# driver.net
KiCad netlist of a schematic drawn in Altium Designer
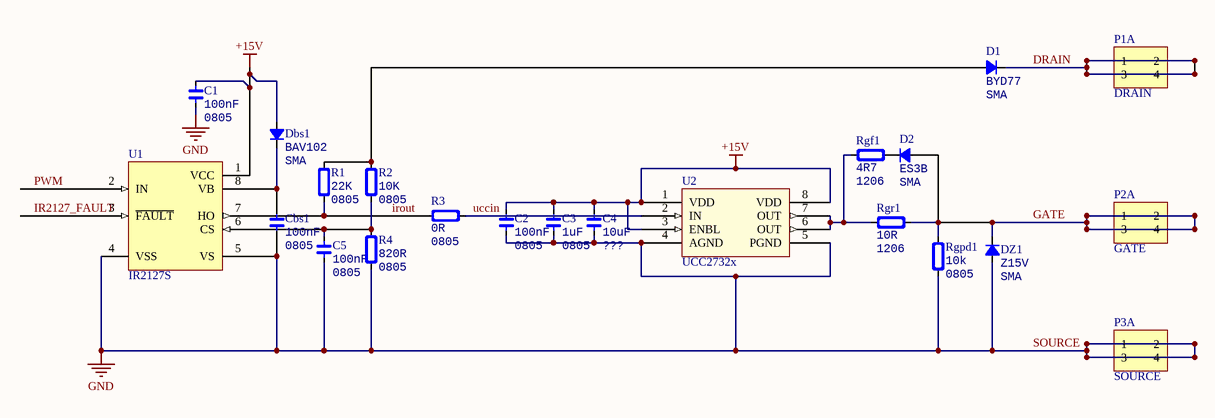
[diagram p0: driver.SchDoc]

(export (version "E")
  (design (tool "Eeschema 10.0.6"))
  (components
    (comp (ref "C1")
      (value "100nF")
      (footprint "0805C")
      (description "Capacitor")
      (fields (field (name "TYPE") "0805"))
      (libsource (lib "SCH_Passive") (part "Cap_0805"))
    )
    (comp (ref "C2")
      (value "100nF")
      (footprint "0805C")
      (description "Capacitor")
      (fields (field (name "TYPE") "0805"))
      (libsource (lib "SCH_Passive") (part "Cap_0805"))
    )
    (comp (ref "C3")
      (value "1uF")
      (footprint "0805C")
      (description "Capacitor")
      (fields (field (name "TYPE") "0805"))
      (libsource (lib "SCH_Passive") (part "Cap_0805"))
    )
    (comp (ref "C4")
      (value "10uF")
      (footprint "0805C")
      (description "Capacitor")
      (fields (field (name "TYPE") "???"))
      (libsource (lib "SCH_Passive") (part "Cap_0805"))
    )
    (comp (ref "C5")
      (value "100nF")
      (footprint "0805C")
      (description "Capacitor")
      (fields (field (name "TYPE") "0805"))
      (libsource (lib "SCH_Passive") (part "Cap_0805"))
    )
    (comp (ref "Cbs1")
      (value "100nF")
      (footprint "0805C")
      (description "Capacitor")
      (fields (field (name "TYPE") "0805"))
      (libsource (lib "SCH_Passive") (part "Cap_0805"))
    )
    (comp (ref "D1")
      (value "BYD77")
      (footprint "DSO-C2/X2.3")
      (description "Diode")
      (fields (field (name "TYPE") "SMA"))
      (libsource (lib "SCH_Active") (part "Diode_SMA"))
    )
    (comp (ref "D2")
      (value "ES3B")
      (footprint "DSO-C2/X2.3")
      (description "Diode")
      (fields (field (name "TYPE") "SMA"))
      (libsource (lib "SCH_Active") (part "Diode_SMA"))
    )
    (comp (ref "Dbs1")
      (value "BAV102")
      (footprint "DSO-C2/X2.3")
      (description "Diode")
      (fields (field (name "TYPE") "SMA"))
      (libsource (lib "SCH_Active") (part "Diode_SMA"))
    )
    (comp (ref "DZ1")
      (value "Z15V")
      (footprint "DSO-C2/X2.3")
      (description "Diode")
      (fields (field (name "TYPE") "SMA"))
      (libsource (lib "SCH_Active") (part "Diode_SMA"))
    )
    (comp (ref "P1A")
      (value "DRAIN")
      (footprint "HDR2X2")
      (description "Header, 2-Pin, Dual row")
      (fields (field (name "PUBLISHER") "Altium Limited"))
      (libsource (lib "Miscellaneous Connectors") (part "Header 2X2"))
    )
    (comp (ref "P2A")
      (value "GATE")
      (footprint "HDR2X2")
      (description "Header, 2-Pin, Dual row")
      (fields (field (name "PUBLISHER") "Altium Limited"))
      (libsource (lib "Miscellaneous Connectors") (part "Header 2X2"))
    )
    (comp (ref "P3A")
      (value "SOURCE")
      (footprint "HDR2X2")
      (description "Header, 2-Pin, Dual row")
      (fields (field (name "PUBLISHER") "Altium Limited"))
      (libsource (lib "Miscellaneous Connectors") (part "Header 2X2"))
    )
    (comp (ref "R1")
      (value "22K")
      (footprint "0805R")
      (description "Resistor")
      (fields (field (name "TYPE") "0805"))
      (libsource (lib "SCH_Passive") (part "Res_0805"))
    )
    (comp (ref "R2")
      (value "10K")
      (footprint "0805R")
      (description "Resistor")
      (fields (field (name "TYPE") "0805"))
      (libsource (lib "SCH_Passive") (part "Res_0805"))
    )
    (comp (ref "R3")
      (value "0R")
      (footprint "0805R")
      (description "Resistor")
      (fields (field (name "TYPE") "0805"))
      (libsource (lib "SCH_Passive") (part "Res_0805"))
    )
    (comp (ref "R4")
      (value "820R")
      (footprint "0805R")
      (description "Resistor")
      (fields (field (name "TYPE") "0805"))
      (libsource (lib "SCH_Passive") (part "Res_0805"))
    )
    (comp (ref "Rgf1")
      (value "4R7")
      (footprint "RESC3225L")
      (description "Resistor")
      (fields (field (name "TYPE") "1206"))
      (libsource (lib "SCH_Passive") (part "Res_0805"))
    )
    (comp (ref "Rgpd1")
      (value "10k")
      (footprint "0805R")
      (description "Resistor")
      (fields (field (name "TYPE") "0805"))
      (libsource (lib "SCH_Passive") (part "Res_0805"))
    )
    (comp (ref "Rgr1")
      (value "10R")
      (footprint "RESC3225L")
      (description "Resistor")
      (fields (field (name "TYPE") "1206"))
      (libsource (lib "SCH_Passive") (part "Res_0805"))
    )
    (comp (ref "U1")
      (value "IR2127S")
      (footprint "SOIC08-150(50)")
      (description "Current Sensing Single Channel Driver")
      (fields (field (name "PUBLISHER") "Altium Limited"))
      (libsource (lib "IR Interface MOSFET Driver") (part "IR2127S"))
    )
    (comp (ref "U2")
      (value "UCC2732x")
      (footprint "SOIC08-Thermal")
      (libsource (lib "Zenite_Symbols") (part "UCC2732x"))
    )
  )
  (nets
    (net (code "1") (name "+15V") (class "Default")
      (node (ref "C1") (pin "1") (pinfunction "1_1") (pintype "passive"))
      (node (ref "C2") (pin "1") (pinfunction "1_1") (pintype "passive"))
      (node (ref "C3") (pin "1") (pinfunction "1_1") (pintype "passive"))
      (node (ref "C4") (pin "1") (pinfunction "1_1") (pintype "passive"))
      (node (ref "Dbs1") (pin "1") (pinfunction "A_1") (pintype "passive"))
      (node (ref "U1") (pin "1") (pinfunction "VCC_1") (pintype "power_in"))
      (node (ref "U2") (pin "1") (pinfunction "VDD_1") (pintype "power_in"))
      (node (ref "U2") (pin "3") (pinfunction "ENBL_3") (pintype "input"))
      (node (ref "U2") (pin "8") (pinfunction "VDD_8") (pintype "power_in"))
    )
    (net (code "2") (name "/DRAIN") (class "Default")
      (node (ref "D1") (pin "2") (pinfunction "K_2") (pintype "passive"))
      (node (ref "P1A") (pin "1") (pinfunction "1_1") (pintype "passive"))
      (node (ref "P1A") (pin "2") (pinfunction "2_2") (pintype "passive"))
      (node (ref "P1A") (pin "3") (pinfunction "3_3") (pintype "passive"))
      (node (ref "P1A") (pin "4") (pinfunction "4_4") (pintype "passive"))
    )
    (net (code "3") (name "/GATE") (class "Default")
      (node (ref "D2") (pin "1") (pinfunction "A_1") (pintype "passive"))
      (node (ref "DZ1") (pin "2") (pinfunction "K_2") (pintype "passive"))
      (node (ref "P2A") (pin "1") (pinfunction "1_1") (pintype "passive"))
      (node (ref "P2A") (pin "2") (pinfunction "2_2") (pintype "passive"))
      (node (ref "P2A") (pin "3") (pinfunction "3_3") (pintype "passive"))
      (node (ref "P2A") (pin "4") (pinfunction "4_4") (pintype "passive"))
      (node (ref "Rgpd1") (pin "1") (pinfunction "1_1") (pintype "passive"))
      (node (ref "Rgr1") (pin "1") (pinfunction "1_1") (pintype "passive"))
    )
    (net (code "4") (name "/IR2127_FAULT") (class "Default")
      (node (ref "U1") (pin "3") (pinfunction "~{FAULT}_3") (pintype "input"))
    )
    (net (code "5") (name "/PWM") (class "Default")
      (node (ref "U1") (pin "2") (pinfunction "IN_2") (pintype "input"))
    )
    (net (code "6") (name "/irout") (class "Default")
      (node (ref "R1") (pin "2") (pinfunction "2_2") (pintype "passive"))
      (node (ref "R3") (pin "2") (pinfunction "2_2") (pintype "passive"))
      (node (ref "U1") (pin "7") (pinfunction "HO_7") (pintype "output"))
    )
    (net (code "7") (name "/uccin") (class "Default")
      (node (ref "R3") (pin "1") (pinfunction "1_1") (pintype "passive"))
      (node (ref "U2") (pin "2") (pinfunction "IN_2") (pintype "input"))
    )
    (net (code "8") (name "GND") (class "Default")
      (node (ref "C1") (pin "2") (pinfunction "2_2") (pintype "passive"))
      (node (ref "C2") (pin "2") (pinfunction "2_2") (pintype "passive"))
      (node (ref "C3") (pin "2") (pinfunction "2_2") (pintype "passive"))
      (node (ref "C4") (pin "2") (pinfunction "2_2") (pintype "passive"))
      (node (ref "C5") (pin "2") (pinfunction "2_2") (pintype "passive"))
      (node (ref "Cbs1") (pin "2") (pinfunction "2_2") (pintype "passive"))
      (node (ref "DZ1") (pin "1") (pinfunction "A_1") (pintype "passive"))
      (node (ref "P3A") (pin "1") (pinfunction "1_1") (pintype "passive"))
      (node (ref "P3A") (pin "2") (pinfunction "2_2") (pintype "passive"))
      (node (ref "P3A") (pin "3") (pinfunction "3_3") (pintype "passive"))
      (node (ref "P3A") (pin "4") (pinfunction "4_4") (pintype "passive"))
      (node (ref "R4") (pin "2") (pinfunction "2_2") (pintype "passive"))
      (node (ref "Rgpd1") (pin "2") (pinfunction "2_2") (pintype "passive"))
      (node (ref "U1") (pin "4") (pinfunction "VSS_4") (pintype "power_in"))
      (node (ref "U1") (pin "5") (pinfunction "VS_5") (pintype "power_in"))
      (node (ref "U2") (pin "4") (pinfunction "AGND_4") (pintype "power_in"))
      (node (ref "U2") (pin "5") (pinfunction "PGND_5") (pintype "power_in"))
    )
    (net (code "9") (name "Net-(D1-A)") (class "Default")
      (node (ref "D1") (pin "1") (pinfunction "A_1") (pintype "passive"))
      (node (ref "R1") (pin "1") (pinfunction "1_1") (pintype "passive"))
      (node (ref "R2") (pin "1") (pinfunction "1_1") (pintype "passive"))
    )
    (net (code "10") (name "Net-(D2-K)") (class "Default")
      (node (ref "D2") (pin "2") (pinfunction "K_2") (pintype "passive"))
      (node (ref "Rgf1") (pin "1") (pinfunction "1_1") (pintype "passive"))
    )
    (net (code "11") (name "Net-(Dbs1-K)") (class "Default")
      (node (ref "Cbs1") (pin "1") (pinfunction "1_1") (pintype "passive"))
      (node (ref "Dbs1") (pin "2") (pinfunction "K_2") (pintype "passive"))
      (node (ref "U1") (pin "8") (pinfunction "VB_8") (pintype "power_in"))
    )
    (net (code "12") (name "Net-(Rgf1-Pad2)") (class "Default")
      (node (ref "Rgf1") (pin "2") (pinfunction "2_2") (pintype "passive"))
      (node (ref "Rgr1") (pin "2") (pinfunction "2_2") (pintype "passive"))
      (node (ref "U2") (pin "6") (pinfunction "OUT_6") (pintype "output"))
      (node (ref "U2") (pin "7") (pinfunction "OUT_7") (pintype "output"))
    )
    (net (code "13") (name "Net-(U1-CS)") (class "Default")
      (node (ref "C5") (pin "1") (pinfunction "1_1") (pintype "passive"))
      (node (ref "R2") (pin "2") (pinfunction "2_2") (pintype "passive"))
      (node (ref "R4") (pin "1") (pinfunction "1_1") (pintype "passive"))
      (node (ref "U1") (pin "6") (pinfunction "CS_6") (pintype "input"))
    )
  )
)
